# Fiber_interlock.net
KiCad netlist of a schematic drawn in Altium Designer
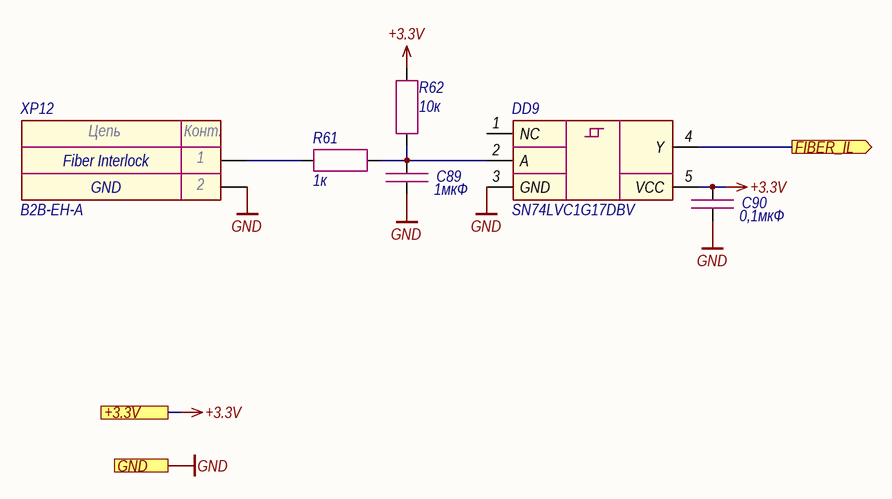
[diagram p0: Fiber_interlock.SchDoc]

(export (version "E")
  (design (tool "Eeschema 10.0.6"))
  (components
    (comp (ref "C89")
      (value "1мкФ")
      (footprint "Pcb_library:CAP_0603")
      (fields (field (name "MANUFACTURER") "Murata"))
      (libsource (lib "Schem_library") (part "Capacitor"))
    )
    (comp (ref "C90")
      (value "0,1мкФ")
      (footprint "Pcb_library:CAP_0603")
      (fields (field (name "MANUFACTURER") "Murata"))
      (libsource (lib "Schem_library") (part "Capacitor"))
    )
    (comp (ref "DD9")
      (value "SN74LVC1G17DBV")
      (footprint "Pcb_library:SOT-23-5")
      (fields (field (name "MANUFACTURER") "Texas Instruments"))
      (libsource (lib "Schem_library") (part "SN74LVC1G17"))
    )
    (comp (ref "R61")
      (value "1к")
      (footprint "Pcb_library:RES_0603")
      (fields (field (name "MANUFACTURER") "Yageo"))
      (libsource (lib "Schem_library") (part "Resistor"))
    )
    (comp (ref "R62")
      (value "10к")
      (footprint "Pcb_library:RES_0603")
      (fields (field (name "MANUFACTURER") "Yageo"))
      (libsource (lib "Schem_library") (part "Resistor"))
    )
    (comp (ref "XP12")
      (value "B2B-EH-A")
      (footprint "Pcb_library:B2B-EH-A")
      (fields (field (name "MANUFACTURER") "JST"))
      (libsource (lib "Schem_library") (part "Connector-2"))
    )
  )
  (nets
    (net (code "1") (name "+3.3V") (class "Default")
      (node (ref "C90") (pin "1") (pinfunction "1_1") (pintype "passive"))
      (node (ref "DD9") (pin "5") (pinfunction "VCC_5") (pintype "passive"))
      (node (ref "R62") (pin "2") (pinfunction "2_2") (pintype "passive"))
    )
    (net (code "2") (name "/FIBER_IL") (class "Default")
      (node (ref "DD9") (pin "4") (pinfunction "Y_4") (pintype "passive"))
    )
    (net (code "3") (name "GND") (class "Default")
      (node (ref "C89") (pin "2") (pinfunction "2_2") (pintype "passive"))
      (node (ref "C90") (pin "2") (pinfunction "2_2") (pintype "passive"))
      (node (ref "DD9") (pin "3") (pinfunction "GND_3") (pintype "passive"))
      (node (ref "XP12") (pin "2") (pintype "passive"))
    )
    (net (code "4") (name "Net-(DD9-A)") (class "Default")
      (node (ref "C89") (pin "1") (pinfunction "1_1") (pintype "passive"))
      (node (ref "DD9") (pin "2") (pinfunction "A_2") (pintype "passive"))
      (node (ref "R61") (pin "2") (pinfunction "2_2") (pintype "passive"))
      (node (ref "R62") (pin "1") (pinfunction "1_1") (pintype "passive"))
    )
    (net (code "5") (name "Net-(R61-Pad1)") (class "Default")
      (node (ref "R61") (pin "1") (pinfunction "1_1") (pintype "passive"))
      (node (ref "XP12") (pin "1") (pintype "passive"))
    )
    (net (code "6") (name "unconnected-(DD9-NC-Pad1)") (class "Default")
      (node (ref "DD9") (pin "1") (pinfunction "NC_1") (pintype "passive"))
    )
  )
)
